# 04C-11.net
KiCad netlist of a schematic drawn in EAGLE
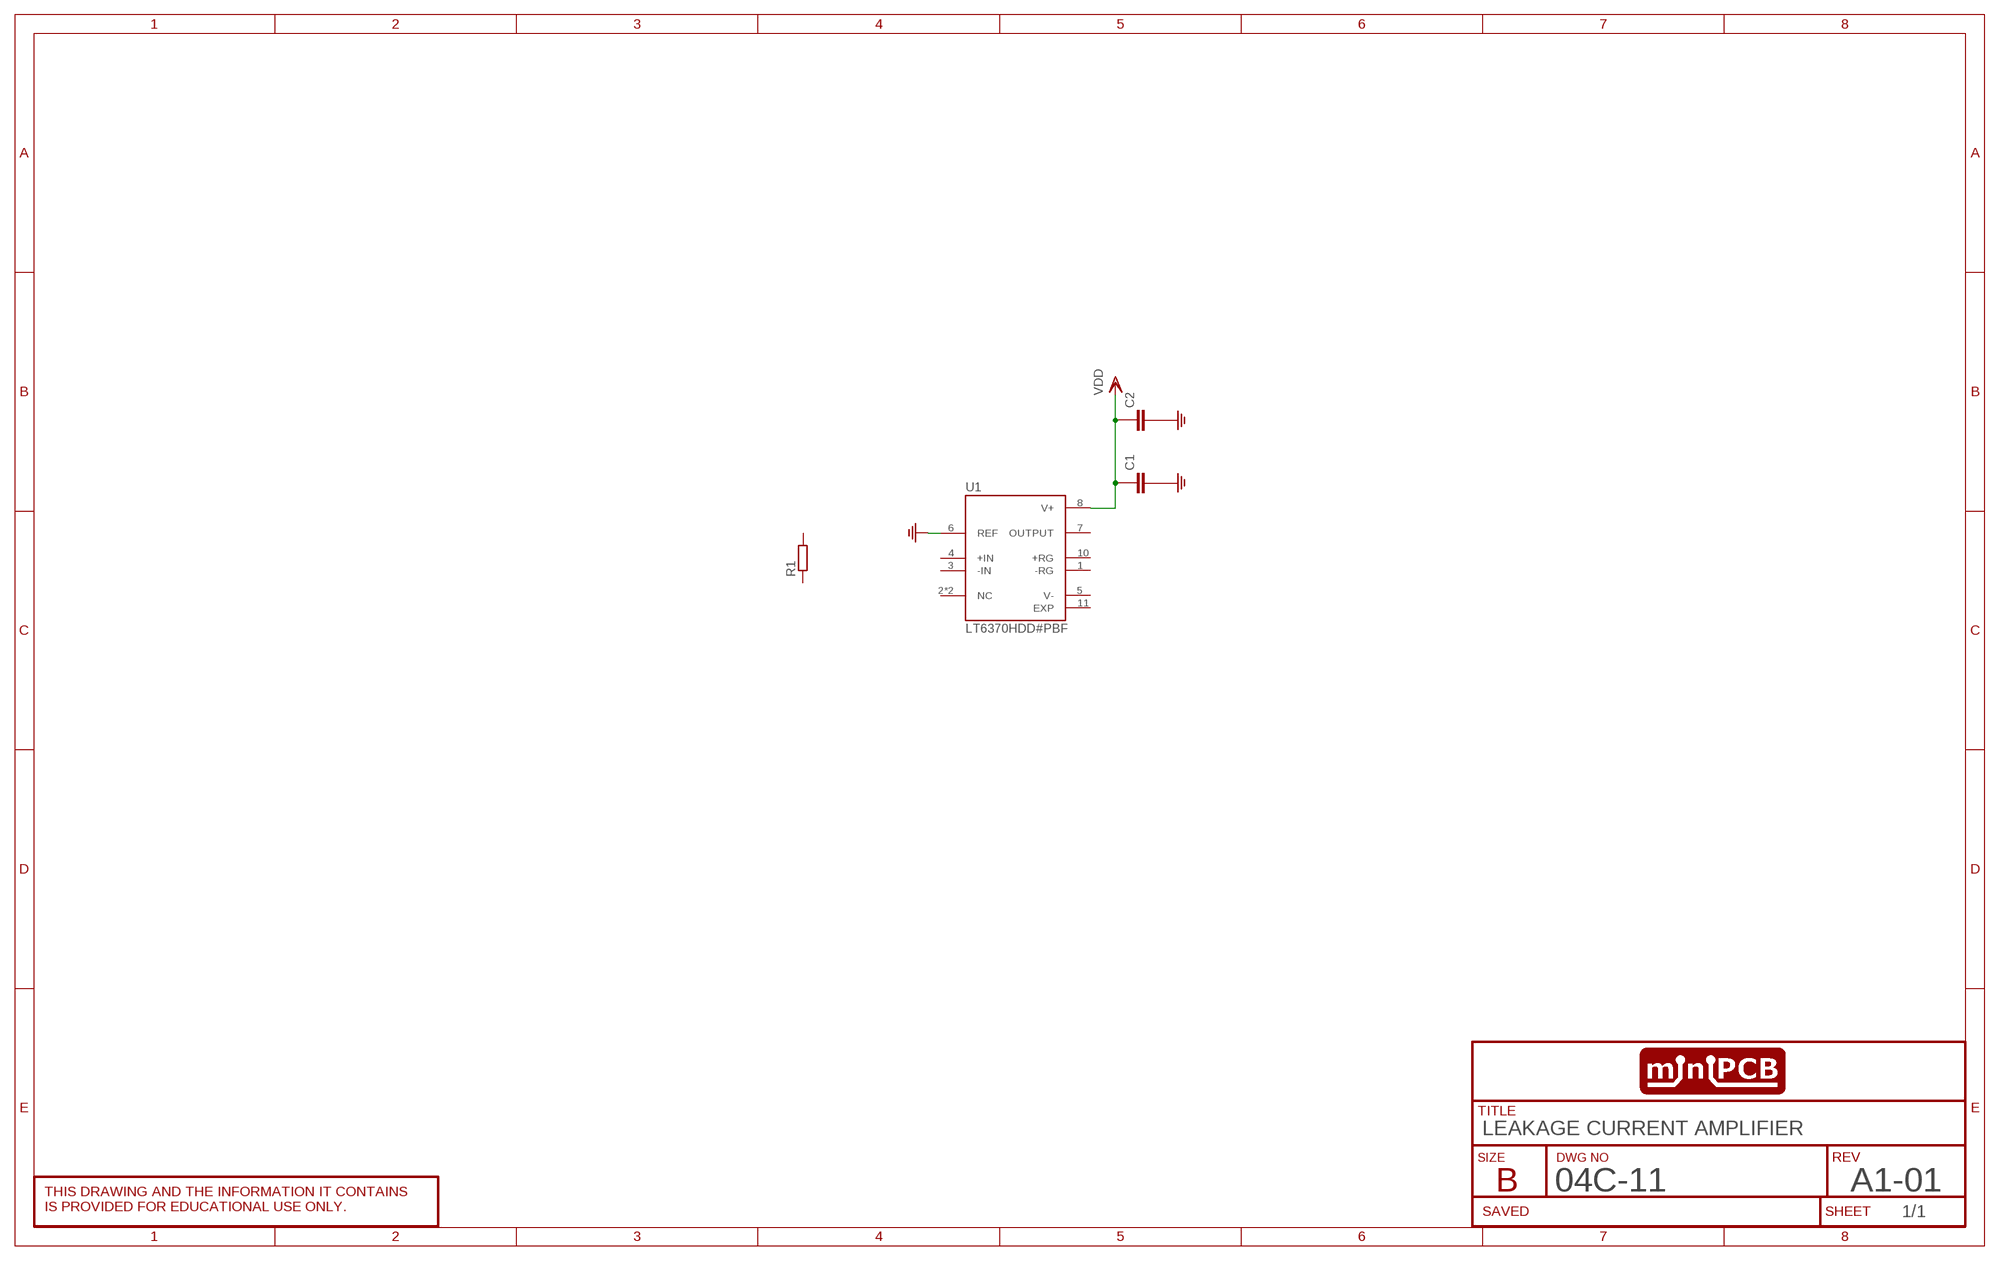
[diagram p0: schematic, sheet 1]

(export (version "E")
  (design (tool "Eeschema 10.0.6"))
  (components
    (comp (ref "C1")
      (value "CAPACITOR0402")
      (footprint "eagle-import:C0402")
      (libsource (lib "eagle-import") (part "CAPACITOR0402"))
    )
    (comp (ref "C2")
      (value "CAPACITOR0402")
      (footprint "eagle-import:C0402")
      (libsource (lib "eagle-import") (part "CAPACITOR0402"))
    )
    (comp (ref "R1")
      (value "RESISTORSMD")
      (footprint "eagle-import:R0805")
      (libsource (lib "eagle-import") (part "RESISTORSMD"))
    )
    (comp (ref "U1")
      (value "LT6370HDD#PBF")
      (footprint "eagle-import:SON50P300X300X80-11N")
      (fields (field (name "MF") "Analog Devices"))
      (libsource (lib "eagle-import") (part "LT6370HDD#PBF"))
    )
  )
  (nets
    (net (code "1") (name "/V-") (class "Default")
      (node (ref "U1") (pin "5") (pinfunction "V-_5") (pintype "power_in"))
    )
    (net (code "2") (name "GND") (class "Default")
      (node (ref "C1") (pin "2") (pinfunction "-_2") (pintype "passive"))
      (node (ref "C2") (pin "2") (pinfunction "-_2") (pintype "passive"))
      (node (ref "U1") (pin "6") (pinfunction "REF_6") (pintype "input"))
    )
    (net (code "3") (name "VDD") (class "Default")
      (node (ref "C1") (pin "1") (pinfunction "+_1") (pintype "passive"))
      (node (ref "C2") (pin "1") (pinfunction "+_1") (pintype "passive"))
      (node (ref "U1") (pin "8") (pinfunction "V+_8") (pintype "power_in"))
    )
    (net (code "4") (name "unconnected-(R1-Pad1)") (class "Default")
      (node (ref "R1") (pin "1") (pinfunction "1_1") (pintype "passive"))
    )
    (net (code "5") (name "unconnected-(R1-Pad2)") (class "Default")
      (node (ref "R1") (pin "2") (pinfunction "2_2") (pintype "passive"))
    )
    (net (code "6") (name "unconnected-(U1-+IN-Pad4)") (class "Default")
      (node (ref "U1") (pin "4") (pinfunction "+IN_4") (pintype "input"))
    )
    (net (code "7") (name "unconnected-(U1-+RG-Pad10)") (class "Default")
      (node (ref "U1") (pin "10") (pinfunction "+RG_10") (pintype "passive"))
    )
    (net (code "8") (name "unconnected-(U1--IN-Pad3)") (class "Default")
      (node (ref "U1") (pin "3") (pinfunction "-IN_3") (pintype "input"))
    )
    (net (code "9") (name "unconnected-(U1--RG-Pad1)") (class "Default")
      (node (ref "U1") (pin "1") (pinfunction "-RG_1") (pintype "passive"))
    )
    (net (code "10") (name "unconnected-(U1-EXP-Pad11)") (class "Default")
      (node (ref "U1") (pin "11") (pinfunction "EXP_11") (pintype "passive"))
    )
    (net (code "11") (name "unconnected-(U1-NC-Pad2)") (class "Default")
      (node (ref "U1") (pin "2") (pinfunction "NC_2") (pintype "no_connect"))
    )
    (net (code "12") (name "unconnected-(U1-NC-Pad9)") (class "Default")
      (node (ref "U1") (pin "9") (pinfunction "NC_9") (pintype "no_connect"))
    )
    (net (code "13") (name "unconnected-(U1-OUTPUT-Pad7)") (class "Default")
      (node (ref "U1") (pin "7") (pinfunction "OUTPUT_7") (pintype "output"))
    )
  )
)
